# wireless_temp.net
KiCad netlist of a schematic drawn in EAGLE
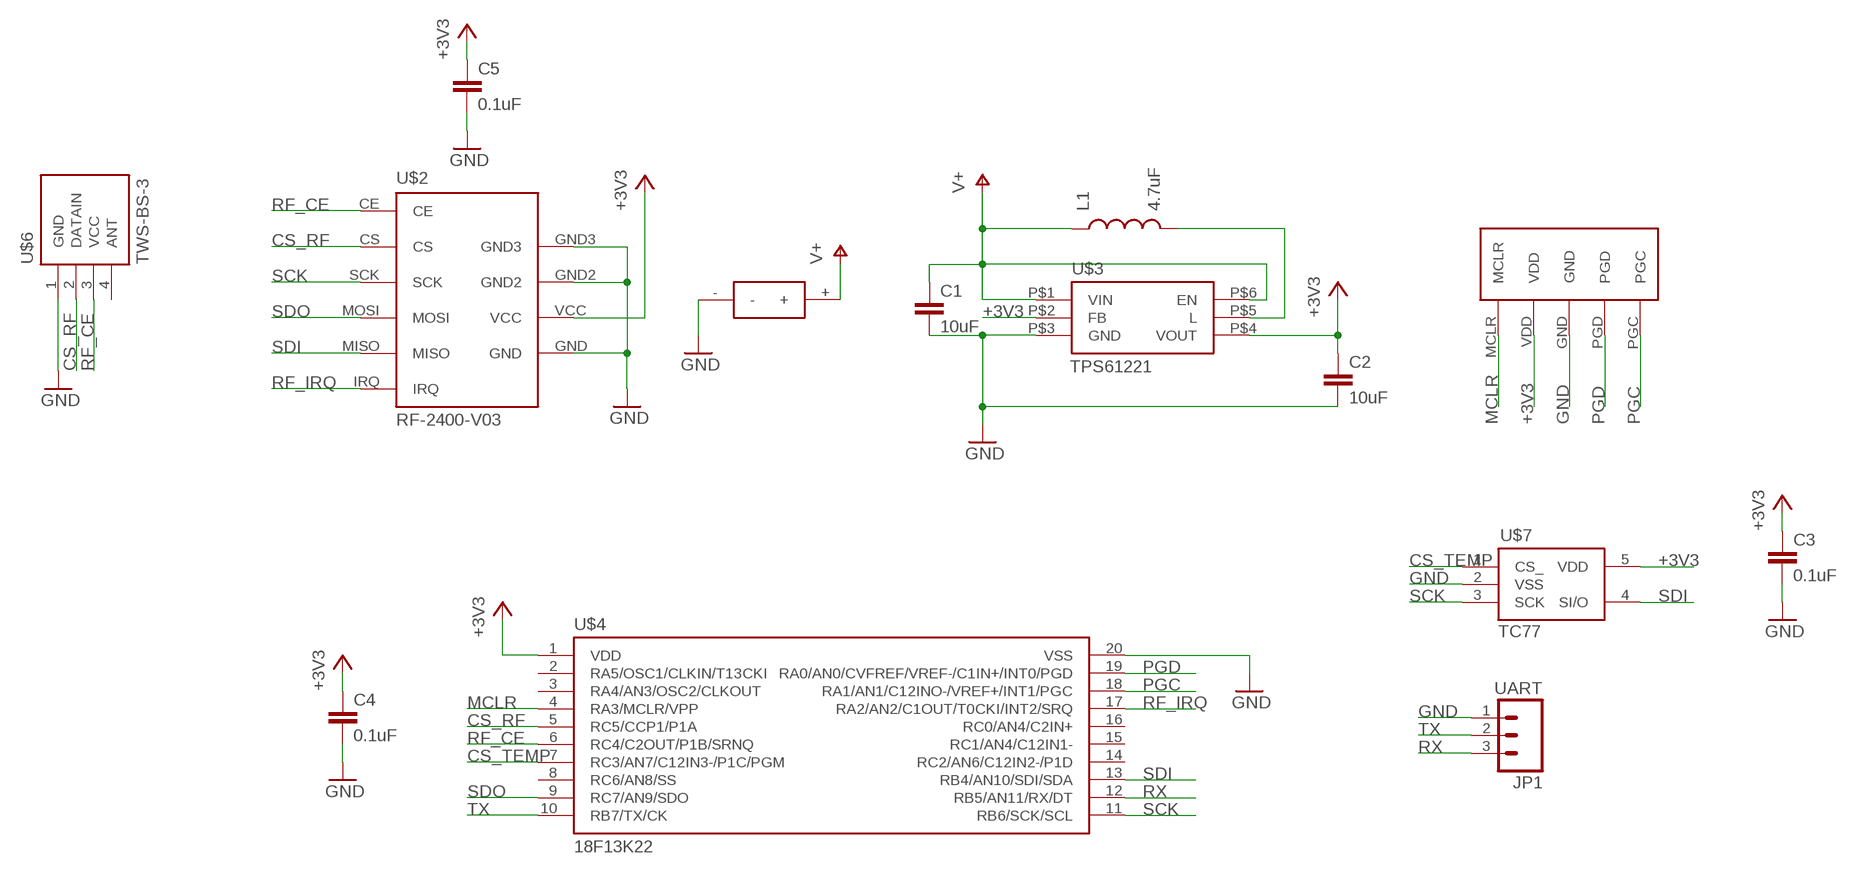
[diagram p0: schematic, sheet 1]

(export (version "E")
  (design (tool "Eeschema 10.0.6"))
  (components
    (comp (ref "C1")
      (value "10uF")
      (footprint "eagle-import:0805")
      (libsource (lib "eagle-import") (part "CAP0805"))
    )
    (comp (ref "C2")
      (value "10uF")
      (footprint "eagle-import:0805")
      (libsource (lib "eagle-import") (part "CAP0805"))
    )
    (comp (ref "C3")
      (value "0.1uF")
      (footprint "eagle-import:0402-CAP")
      (libsource (lib "eagle-import") (part "CAP0402-CAP"))
    )
    (comp (ref "C4")
      (value "0.1uF")
      (footprint "eagle-import:0402-CAP")
      (libsource (lib "eagle-import") (part "CAP0402-CAP"))
    )
    (comp (ref "C5")
      (value "0.1uF")
      (footprint "eagle-import:0402-CAP")
      (libsource (lib "eagle-import") (part "CAP0402-CAP"))
    )
    (comp (ref "JP1")
      (value "UART")
      (footprint "eagle-import:1X03")
      (libsource (lib "eagle-import") (part "M03PTH"))
    )
    (comp (ref "L1")
      (value "4.7uF")
      (footprint "eagle-import:NR3015T")
      (libsource (lib "eagle-import") (part "INDUCTOR"))
    )
    (comp (ref "U$1")
      (value "BAT_HOLDER")
      (footprint "eagle-import:AAA")
      (libsource (lib "eagle-import") (part "BAT_HOLDER"))
    )
    (comp (ref "U$2")
      (value "RF-2400-V03")
      (footprint "eagle-import:RF-2400-V03")
      (libsource (lib "eagle-import") (part "RF-2400-V03"))
    )
    (comp (ref "U$3")
      (value "TPS61221")
      (footprint "eagle-import:SO6")
      (libsource (lib "eagle-import") (part "TPS61221"))
    )
    (comp (ref "U$4")
      (value "18F13K22")
      (footprint "eagle-import:SSOP20")
      (libsource (lib "eagle-import") (part "18F13K22"))
    )
    (comp (ref "U$5")
      (value "PIC-ICSP")
      (footprint "eagle-import:ICSP")
      (libsource (lib "eagle-import") (part "PIC-ICSP"))
    )
    (comp (ref "U$6")
      (value "TWS-BS-3")
      (footprint "eagle-import:TWS-BS-3")
      (libsource (lib "eagle-import") (part "TWS-BS-3"))
    )
    (comp (ref "U$7")
      (value "TC77")
      (footprint "eagle-import:SOT23-5")
      (libsource (lib "eagle-import") (part "TC77"))
    )
  )
  (nets
    (net (code "1") (name "+3V3") (class "Default")
      (node (ref "C2") (pin "1") (pinfunction "1_1") (pintype "passive"))
      (node (ref "C3") (pin "1") (pinfunction "1_1") (pintype "passive"))
      (node (ref "C4") (pin "1") (pinfunction "1_1") (pintype "passive"))
      (node (ref "C5") (pin "1") (pinfunction "1_1") (pintype "passive"))
      (node (ref "U$2") (pin "VCC") (pinfunction "VCC_VCC") (pintype "bidirectional"))
      (node (ref "U$3") (pin "P$2") (pinfunction "FB_P$2") (pintype "bidirectional"))
      (node (ref "U$3") (pin "P$4") (pinfunction "VOUT_P$4") (pintype "bidirectional"))
      (node (ref "U$4") (pin "1") (pinfunction "VDD_1") (pintype "bidirectional"))
      (node (ref "U$5") (pin "VDD") (pinfunction "VDD_VDD") (pintype "bidirectional"))
      (node (ref "U$7") (pin "5") (pinfunction "VDD_5") (pintype "bidirectional"))
    )
    (net (code "2") (name "/CS_RF") (class "Default")
      (node (ref "U$2") (pin "CS") (pinfunction "CS_CS") (pintype "bidirectional"))
      (node (ref "U$4") (pin "5") (pinfunction "RC5/CCP1/P1A_5") (pintype "bidirectional"))
      (node (ref "U$6") (pin "2") (pinfunction "DATAIN_2") (pintype "bidirectional"))
    )
    (net (code "3") (name "/CS_TEMP") (class "Default")
      (node (ref "U$4") (pin "7") (pinfunction "RC3/AN7/C12IN3-/P1C/PGM_7") (pintype "bidirectional"))
      (node (ref "U$7") (pin "1") (pinfunction "CS__1") (pintype "bidirectional"))
    )
    (net (code "4") (name "/MCLR") (class "Default")
      (node (ref "U$4") (pin "4") (pinfunction "RA3/MCLR/VPP_4") (pintype "bidirectional"))
      (node (ref "U$5") (pin "MCLR") (pinfunction "MCLR_MCLR") (pintype "bidirectional"))
    )
    (net (code "5") (name "/PGC") (class "Default")
      (node (ref "U$4") (pin "18") (pinfunction "RA1/AN1/C12INO-/VREF+/INT1/PGC_18") (pintype "bidirectional"))
      (node (ref "U$5") (pin "PGC") (pinfunction "PGC_PGC") (pintype "bidirectional"))
    )
    (net (code "6") (name "/PGD") (class "Default")
      (node (ref "U$4") (pin "19") (pinfunction "RA0/AN0/CVFREF/VREF-/C1IN+/INT0/PGD_19") (pintype "bidirectional"))
      (node (ref "U$5") (pin "PGD") (pinfunction "PGD_PGD") (pintype "bidirectional"))
    )
    (net (code "7") (name "/RF_CE") (class "Default")
      (node (ref "U$2") (pin "CE") (pinfunction "CE_CE") (pintype "bidirectional"))
      (node (ref "U$4") (pin "6") (pinfunction "RC4/C2OUT/P1B/SRNQ_6") (pintype "bidirectional"))
      (node (ref "U$6") (pin "3") (pinfunction "VCC_3") (pintype "bidirectional"))
    )
    (net (code "8") (name "/RF_IRQ") (class "Default")
      (node (ref "U$2") (pin "IRQ") (pinfunction "IRQ_IRQ") (pintype "bidirectional"))
      (node (ref "U$4") (pin "17") (pinfunction "RA2/AN2/C1OUT/T0CKI/INT2/SRQ_17") (pintype "bidirectional"))
    )
    (net (code "9") (name "/RX") (class "Default")
      (node (ref "JP1") (pin "3") (pinfunction "3_3") (pintype "passive"))
      (node (ref "U$4") (pin "12") (pinfunction "RB5/AN11/RX/DT_12") (pintype "bidirectional"))
    )
    (net (code "10") (name "/SCK") (class "Default")
      (node (ref "U$2") (pin "SCK") (pinfunction "SCK_SCK") (pintype "bidirectional"))
      (node (ref "U$4") (pin "11") (pinfunction "RB6/SCK/SCL_11") (pintype "bidirectional"))
      (node (ref "U$7") (pin "3") (pinfunction "SCK_3") (pintype "bidirectional"))
    )
    (net (code "11") (name "/SDI") (class "Default")
      (node (ref "U$2") (pin "MISO") (pinfunction "MISO_MISO") (pintype "bidirectional"))
      (node (ref "U$4") (pin "13") (pinfunction "RB4/AN10/SDI/SDA_13") (pintype "bidirectional"))
      (node (ref "U$7") (pin "4") (pinfunction "SI/O_4") (pintype "bidirectional"))
    )
    (net (code "12") (name "/SDO") (class "Default")
      (node (ref "U$2") (pin "MOSI") (pinfunction "MOSI_MOSI") (pintype "bidirectional"))
      (node (ref "U$4") (pin "9") (pinfunction "RC7/AN9/SDO_9") (pintype "bidirectional"))
    )
    (net (code "13") (name "/TX") (class "Default")
      (node (ref "JP1") (pin "2") (pinfunction "2_2") (pintype "passive"))
      (node (ref "U$4") (pin "10") (pinfunction "RB7/TX/CK_10") (pintype "bidirectional"))
    )
    (net (code "14") (name "GND") (class "Default")
      (node (ref "C1") (pin "2") (pinfunction "2_2") (pintype "passive"))
      (node (ref "C2") (pin "2") (pinfunction "2_2") (pintype "passive"))
      (node (ref "C3") (pin "2") (pinfunction "2_2") (pintype "passive"))
      (node (ref "C4") (pin "2") (pinfunction "2_2") (pintype "passive"))
      (node (ref "C5") (pin "2") (pinfunction "2_2") (pintype "passive"))
      (node (ref "JP1") (pin "1") (pinfunction "1_1") (pintype "passive"))
      (node (ref "U$1") (pin "-") (pinfunction "-_-") (pintype "bidirectional"))
      (node (ref "U$2") (pin "GND") (pinfunction "GND_GND") (pintype "bidirectional"))
      (node (ref "U$2") (pin "GND2") (pinfunction "GND2_GND2") (pintype "bidirectional"))
      (node (ref "U$2") (pin "GND3") (pinfunction "GND3_GND3") (pintype "bidirectional"))
      (node (ref "U$3") (pin "P$3") (pinfunction "GND_P$3") (pintype "bidirectional"))
      (node (ref "U$4") (pin "20") (pinfunction "VSS_20") (pintype "bidirectional"))
      (node (ref "U$5") (pin "GND") (pinfunction "GND_GND") (pintype "bidirectional"))
      (node (ref "U$6") (pin "1") (pinfunction "GND_1") (pintype "bidirectional"))
      (node (ref "U$7") (pin "2") (pinfunction "VSS_2") (pintype "bidirectional"))
    )
    (net (code "15") (name "Net-(L1-2)") (class "Default")
      (node (ref "L1") (pin "P$2") (pinfunction "2_P$2") (pintype "passive"))
      (node (ref "U$3") (pin "P$5") (pinfunction "L_P$5") (pintype "bidirectional"))
    )
    (net (code "16") (name "V+") (class "Default")
      (node (ref "C1") (pin "1") (pinfunction "1_1") (pintype "passive"))
      (node (ref "L1") (pin "P$1") (pinfunction "1_P$1") (pintype "passive"))
      (node (ref "U$1") (pin "+") (pinfunction "+_+") (pintype "bidirectional"))
      (node (ref "U$3") (pin "P$1") (pinfunction "VIN_P$1") (pintype "bidirectional"))
      (node (ref "U$3") (pin "P$6") (pinfunction "EN_P$6") (pintype "bidirectional"))
    )
    (net (code "17") (name "unconnected-(U$4-RA4{slash}AN3{slash}OSC2{slash}CLKOUT-Pad3)") (class "Default")
      (node (ref "U$4") (pin "3") (pinfunction "RA4/AN3/OSC2/CLKOUT_3") (pintype "bidirectional"))
    )
    (net (code "18") (name "unconnected-(U$4-RA5{slash}OSC1{slash}CLKIN{slash}T13CKI-Pad2)") (class "Default")
      (node (ref "U$4") (pin "2") (pinfunction "RA5/OSC1/CLKIN/T13CKI_2") (pintype "bidirectional"))
    )
    (net (code "19") (name "unconnected-(U$4-RC0{slash}AN4{slash}C2IN+-Pad16)") (class "Default")
      (node (ref "U$4") (pin "16") (pinfunction "RC0/AN4/C2IN+_16") (pintype "bidirectional"))
    )
    (net (code "20") (name "unconnected-(U$4-RC1{slash}AN4{slash}C12IN1--Pad15)") (class "Default")
      (node (ref "U$4") (pin "15") (pinfunction "RC1/AN4/C12IN1-_15") (pintype "bidirectional"))
    )
    (net (code "21") (name "unconnected-(U$4-RC2{slash}AN6{slash}C12IN2-{slash}P1D-Pad14)") (class "Default")
      (node (ref "U$4") (pin "14") (pinfunction "RC2/AN6/C12IN2-/P1D_14") (pintype "bidirectional"))
    )
    (net (code "22") (name "unconnected-(U$4-RC6{slash}AN8{slash}SS-Pad8)") (class "Default")
      (node (ref "U$4") (pin "8") (pinfunction "RC6/AN8/SS_8") (pintype "bidirectional"))
    )
    (net (code "23") (name "unconnected-(U$6-ANT-Pad4)") (class "Default")
      (node (ref "U$6") (pin "4") (pinfunction "ANT_4") (pintype "bidirectional"))
    )
  )
)
